# LCD_backpack.net
KiCad netlist of a schematic drawn in EAGLE
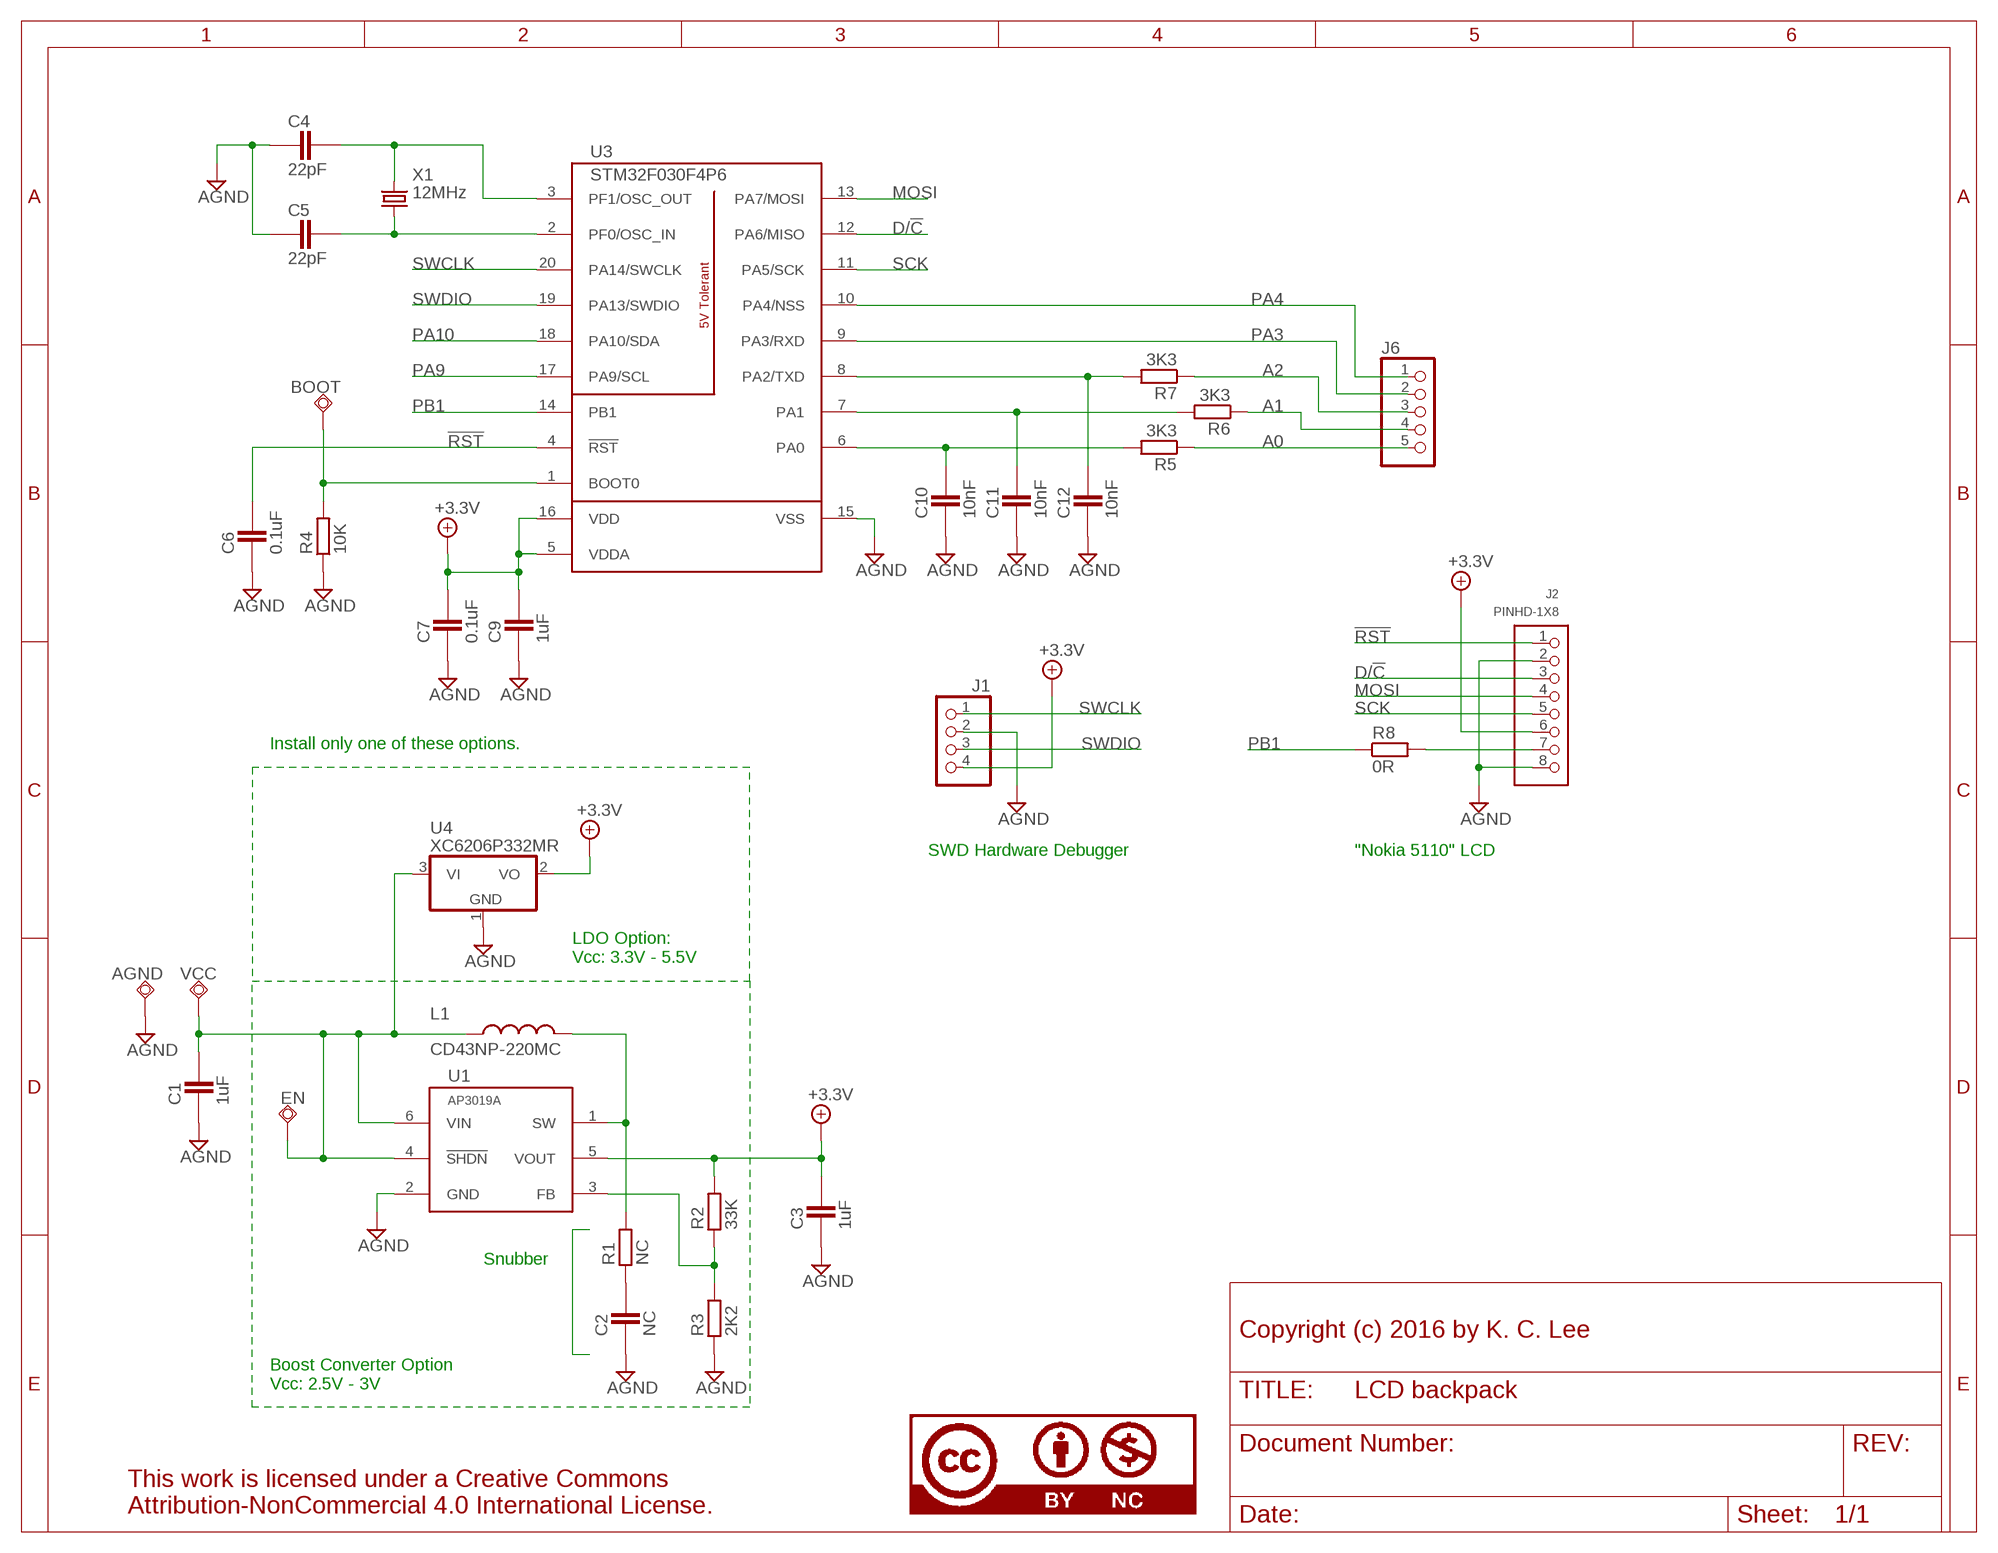
[diagram p0: schematic, sheet 1]

(export (version "E")
  (design (tool "Eeschema 10.0.6"))
  (components
    (comp (ref "AGND")
      (value "TPSQTP10SQ")
      (footprint "eagle-import:TP10SQ")
      (fields (field (name "PARTNO") "TESTPAD"))
      (libsource (lib "eagle-import") (part "TPSQTP10SQ"))
    )
    (comp (ref "BOOT")
      (value "TPSQTP10SQ")
      (footprint "eagle-import:TP10SQ")
      (fields (field (name "PARTNO") "TESTPAD"))
      (libsource (lib "eagle-import") (part "TPSQTP10SQ"))
    )
    (comp (ref "C1")
      (value "1uF")
      (footprint "eagle-import:CAPC1608X92N")
      (fields (field (name "PARTNO") "STOCK: 1UF/10V 20% TDK"))
      (libsource (lib "eagle-import") (part "CAPACITOR_0603"))
    )
    (comp (ref "C2")
      (value "NC")
      (footprint "eagle-import:CAPC1608X92N")
      (libsource (lib "eagle-import") (part "CAPACITOR_0603"))
    )
    (comp (ref "C3")
      (value "1uF")
      (footprint "eagle-import:CAPC1608X92N")
      (fields (field (name "PARTNO") "STOCK: 1UF/10V 20% TDK"))
      (libsource (lib "eagle-import") (part "CAPACITOR_0603"))
    )
    (comp (ref "C4")
      (value "22pF")
      (footprint "eagle-import:CAPC1608X92N")
      (libsource (lib "eagle-import") (part "CAPACITOR_0603"))
    )
    (comp (ref "C5")
      (value "22pF")
      (footprint "eagle-import:CAPC1608X92N")
      (libsource (lib "eagle-import") (part "CAPACITOR_0603"))
    )
    (comp (ref "C6")
      (value "0.1uF")
      (footprint "eagle-import:CAPC1608X92N")
      (libsource (lib "eagle-import") (part "CAPACITOR_0603"))
    )
    (comp (ref "C7")
      (value "0.1uF")
      (footprint "eagle-import:CAPC1608X92N")
      (libsource (lib "eagle-import") (part "CAPACITOR_0603"))
    )
    (comp (ref "C9")
      (value "1uF")
      (footprint "eagle-import:CAPC1608X92N")
      (fields (field (name "PARTNO") "STOCK: 1UF/10V 20% TDK"))
      (libsource (lib "eagle-import") (part "CAPACITOR_0603"))
    )
    (comp (ref "C10")
      (value "10nF")
      (footprint "eagle-import:CAPC1608X92N")
      (libsource (lib "eagle-import") (part "CAPACITOR_0603"))
    )
    (comp (ref "C11")
      (value "10nF")
      (footprint "eagle-import:CAPC1608X92N")
      (libsource (lib "eagle-import") (part "CAPACITOR_0603"))
    )
    (comp (ref "C12")
      (value "10nF")
      (footprint "eagle-import:CAPC1608X92N")
      (libsource (lib "eagle-import") (part "CAPACITOR_0603"))
    )
    (comp (ref "EN")
      (value "TPSQTP06SQ")
      (footprint "eagle-import:TP06SQ")
      (fields (field (name "PARTNO") "TESTPAD"))
      (libsource (lib "eagle-import") (part "TPSQTP06SQ"))
    )
    (comp (ref "J1")
      (value "PINHD-1X4_2.54")
      (footprint "eagle-import:1X04")
      (fields (field (name "PARTNO") "1x04 header 2.54mm"))
      (libsource (lib "eagle-import") (part "PINHD-1X4_2.54"))
    )
    (comp (ref "J2")
      (value "PINHD-1X8")
      (footprint "eagle-import:1X08")
      (fields (field (name "PARTNO") "1x08 header 2.54mm"))
      (libsource (lib "eagle-import") (part "PINHD-1X8"))
    )
    (comp (ref "J6")
      (value "PINHD-1X5_2.00")
      (footprint "eagle-import:1X05M")
      (fields (field (name "PARTNO") "1X5 header 2MM"))
      (libsource (lib "eagle-import") (part "PINHD-1X5_2.00"))
    )
    (comp (ref "L1")
      (value "CD43NP-220MC")
      (footprint "eagle-import:CD43")
      (fields (field (name "PARTNO") "DK: 587-1626-1-ND"))
      (libsource (lib "eagle-import") (part "CD43"))
    )
    (comp (ref "LICENSE1")
      (value "CC-BY-NCNONE")
      (footprint "eagle-import:CC-NONE")
      (libsource (lib "eagle-import") (part "CC-BY-NCNONE"))
    )
    (comp (ref "R1")
      (value "NC")
      (footprint "eagle-import:RESC1608X55N")
      (libsource (lib "eagle-import") (part "RESISTOR_0603"))
    )
    (comp (ref "R2")
      (value "33K")
      (footprint "eagle-import:RESC1608X55N")
      (libsource (lib "eagle-import") (part "RESISTOR_0603"))
    )
    (comp (ref "R3")
      (value "2K2")
      (footprint "eagle-import:RESC1608X55N")
      (libsource (lib "eagle-import") (part "RESISTOR_0603"))
    )
    (comp (ref "R4")
      (value "10K")
      (footprint "eagle-import:RESC1608X55N")
      (libsource (lib "eagle-import") (part "RESISTOR_0603"))
    )
    (comp (ref "R5")
      (value "3K3")
      (footprint "eagle-import:RESC1608X55N")
      (libsource (lib "eagle-import") (part "RESISTOR_0603"))
    )
    (comp (ref "R6")
      (value "3K3")
      (footprint "eagle-import:RESC1608X55N")
      (libsource (lib "eagle-import") (part "RESISTOR_0603"))
    )
    (comp (ref "R7")
      (value "3K3")
      (footprint "eagle-import:RESC1608X55N")
      (libsource (lib "eagle-import") (part "RESISTOR_0603"))
    )
    (comp (ref "R8")
      (value "0R")
      (footprint "eagle-import:RESC1608X55N")
      (libsource (lib "eagle-import") (part "RESISTOR_0603"))
    )
    (comp (ref "U1")
      (value "AP3019A")
      (footprint "eagle-import:SOT26")
      (fields (field (name "PARTNO") "AP3019AKTR-G1"))
      (libsource (lib "eagle-import") (part "AP3019"))
    )
    (comp (ref "U3")
      (value "STM32F030F4P6")
      (footprint "eagle-import:TSSOP20")
      (libsource (lib "eagle-import") (part "STM32F030F4P6"))
    )
    (comp (ref "U4")
      (value "XC6206P332MR")
      (footprint "eagle-import:SOT95P280X135-3N")
      (libsource (lib "eagle-import") (part "MCP1700/TT"))
    )
    (comp (ref "VCC")
      (value "TPSQTP10SQ")
      (footprint "eagle-import:TP10SQ")
      (fields (field (name "PARTNO") "TESTPAD"))
      (libsource (lib "eagle-import") (part "TPSQTP10SQ"))
    )
    (comp (ref "X1")
      (value "12MHz")
      (footprint "eagle-import:HC49U-V")
      (libsource (lib "eagle-import") (part "CRYSTALHC49U-V"))
    )
  )
  (nets
    (net (code "1") (name "+3.3V") (class "Default")
      (node (ref "C3") (pin "2") (pinfunction "2_2") (pintype "passive"))
      (node (ref "C7") (pin "2") (pinfunction "2_2") (pintype "passive"))
      (node (ref "C9") (pin "2") (pinfunction "2_2") (pintype "passive"))
      (node (ref "J1") (pin "4") (pinfunction "4_4") (pintype "passive"))
      (node (ref "J2") (pin "6") (pinfunction "P$6_6") (pintype "bidirectional"))
      (node (ref "R2") (pin "2") (pinfunction "2_2") (pintype "passive"))
      (node (ref "U1") (pin "5") (pinfunction "VOUT_5") (pintype "bidirectional"))
      (node (ref "U3") (pin "16") (pinfunction "VDD_16") (pintype "input"))
      (node (ref "U3") (pin "5") (pinfunction "VDDA_5") (pintype "input"))
      (node (ref "U4") (pin "2") (pinfunction "VO_2") (pintype "passive"))
    )
    (net (code "2") (name "/A0") (class "Default")
      (node (ref "J6") (pin "5") (pinfunction "5_5") (pintype "passive"))
      (node (ref "R5") (pin "1") (pinfunction "1_1") (pintype "passive"))
    )
    (net (code "3") (name "/A1") (class "Default")
      (node (ref "J6") (pin "4") (pinfunction "4_4") (pintype "passive"))
      (node (ref "R6") (pin "1") (pinfunction "1_1") (pintype "passive"))
    )
    (net (code "4") (name "/A2") (class "Default")
      (node (ref "J6") (pin "3") (pinfunction "3_3") (pintype "passive"))
      (node (ref "R7") (pin "1") (pinfunction "1_1") (pintype "passive"))
    )
    (net (code "5") (name "/D{slash}~{C}") (class "Default")
      (node (ref "J2") (pin "3") (pinfunction "P$3_3") (pintype "bidirectional"))
      (node (ref "U3") (pin "12") (pinfunction "PA6/MISO_12") (pintype "bidirectional"))
    )
    (net (code "6") (name "/MOSI") (class "Default")
      (node (ref "J2") (pin "4") (pinfunction "P$4_4") (pintype "bidirectional"))
      (node (ref "U3") (pin "13") (pinfunction "PA7/MOSI_13") (pintype "bidirectional"))
    )
    (net (code "8") (name "/PA3") (class "Default")
      (node (ref "J6") (pin "2") (pinfunction "2_2") (pintype "passive"))
      (node (ref "U3") (pin "9") (pinfunction "PA3/RXD_9") (pintype "bidirectional"))
    )
    (net (code "9") (name "/PA4") (class "Default")
      (node (ref "J6") (pin "1") (pinfunction "1_1") (pintype "passive"))
      (node (ref "U3") (pin "10") (pinfunction "PA4/NSS_10") (pintype "bidirectional"))
    )
    (net (code "10") (name "/PA9") (class "Default")
      (node (ref "U3") (pin "17") (pinfunction "PA9/SCL_17") (pintype "bidirectional"))
    )
    (net (code "11") (name "/PA10") (class "Default")
      (node (ref "U3") (pin "18") (pinfunction "PA10/SDA_18") (pintype "bidirectional"))
    )
    (net (code "12") (name "/PB1") (class "Default")
      (node (ref "R8") (pin "1") (pinfunction "1_1") (pintype "passive"))
      (node (ref "U3") (pin "14") (pinfunction "PB1_14") (pintype "bidirectional"))
    )
    (net (code "13") (name "/SCK") (class "Default")
      (node (ref "J2") (pin "5") (pinfunction "P$5_5") (pintype "bidirectional"))
      (node (ref "U3") (pin "11") (pinfunction "PA5/SCK_11") (pintype "bidirectional"))
    )
    (net (code "14") (name "/SWCLK") (class "Default")
      (node (ref "J1") (pin "1") (pinfunction "1_1") (pintype "passive"))
      (node (ref "U3") (pin "20") (pinfunction "PA14/SWCLK_20") (pintype "bidirectional"))
    )
    (net (code "15") (name "/SWDIO") (class "Default")
      (node (ref "J1") (pin "3") (pinfunction "3_3") (pintype "passive"))
      (node (ref "U3") (pin "19") (pinfunction "PA13/SWDIO_19") (pintype "bidirectional"))
    )
    (net (code "16") (name "/~{RST}") (class "Default")
      (node (ref "C6") (pin "2") (pinfunction "2_2") (pintype "passive"))
      (node (ref "J2") (pin "1") (pinfunction "P$1_1") (pintype "bidirectional"))
      (node (ref "U3") (pin "4") (pinfunction "~{RST}_4") (pintype "input"))
    )
    (net (code "17") (name "AGND") (class "Default")
      (node (ref "AGND") (pin "TP") (pinfunction "TP_TP") (pintype "input"))
      (node (ref "C1") (pin "1") (pinfunction "1_1") (pintype "passive"))
      (node (ref "C10") (pin "1") (pinfunction "1_1") (pintype "passive"))
      (node (ref "C11") (pin "1") (pinfunction "1_1") (pintype "passive"))
      (node (ref "C12") (pin "1") (pinfunction "1_1") (pintype "passive"))
      (node (ref "C2") (pin "1") (pinfunction "1_1") (pintype "passive"))
      (node (ref "C3") (pin "1") (pinfunction "1_1") (pintype "passive"))
      (node (ref "C4") (pin "1") (pinfunction "1_1") (pintype "passive"))
      (node (ref "C5") (pin "1") (pinfunction "1_1") (pintype "passive"))
      (node (ref "C6") (pin "1") (pinfunction "1_1") (pintype "passive"))
      (node (ref "C7") (pin "1") (pinfunction "1_1") (pintype "passive"))
      (node (ref "C9") (pin "1") (pinfunction "1_1") (pintype "passive"))
      (node (ref "J1") (pin "2") (pinfunction "2_2") (pintype "passive"))
      (node (ref "J2") (pin "2") (pinfunction "P$2_2") (pintype "bidirectional"))
      (node (ref "J2") (pin "8") (pinfunction "P$8_8") (pintype "bidirectional"))
      (node (ref "R3") (pin "1") (pinfunction "1_1") (pintype "passive"))
      (node (ref "R4") (pin "1") (pinfunction "1_1") (pintype "passive"))
      (node (ref "U1") (pin "2") (pinfunction "GND_2") (pintype "bidirectional"))
      (node (ref "U3") (pin "15") (pinfunction "VSS_15") (pintype "input"))
      (node (ref "U4") (pin "1") (pinfunction "GND_1") (pintype "passive"))
    )
    (net (code "18") (name "Net-(C2-Pad2)") (class "Default")
      (node (ref "C2") (pin "2") (pinfunction "2_2") (pintype "passive"))
      (node (ref "R1") (pin "1") (pinfunction "1_1") (pintype "passive"))
    )
    (net (code "19") (name "Net-(J2-P$7)") (class "Default")
      (node (ref "J2") (pin "7") (pinfunction "P$7_7") (pintype "bidirectional"))
      (node (ref "R8") (pin "2") (pinfunction "2_2") (pintype "passive"))
    )
    (net (code "20") (name "Net-(U1-FB)") (class "Default")
      (node (ref "R2") (pin "1") (pinfunction "1_1") (pintype "passive"))
      (node (ref "R3") (pin "2") (pinfunction "2_2") (pintype "passive"))
      (node (ref "U1") (pin "3") (pinfunction "FB_3") (pintype "bidirectional"))
    )
    (net (code "21") (name "Net-(U1-SW)") (class "Default")
      (node (ref "L1") (pin "1") (pinfunction "1_1") (pintype "passive"))
      (node (ref "R1") (pin "2") (pinfunction "2_2") (pintype "passive"))
      (node (ref "U1") (pin "1") (pinfunction "SW_1") (pintype "bidirectional"))
    )
    (net (code "22") (name "Net-(U1-VIN)") (class "Default")
      (node (ref "C1") (pin "2") (pinfunction "2_2") (pintype "passive"))
      (node (ref "EN") (pin "TP") (pinfunction "TP_TP") (pintype "input"))
      (node (ref "L1") (pin "2") (pinfunction "2_2") (pintype "passive"))
      (node (ref "U1") (pin "4") (pinfunction "~{SHDN}_4") (pintype "bidirectional"))
      (node (ref "U1") (pin "6") (pinfunction "VIN_6") (pintype "bidirectional"))
      (node (ref "U4") (pin "3") (pinfunction "VI_3") (pintype "input"))
      (node (ref "VCC") (pin "TP") (pinfunction "TP_TP") (pintype "input"))
    )
    (net (code "23") (name "Net-(U3-BOOT0)") (class "Default")
      (node (ref "BOOT") (pin "TP") (pinfunction "TP_TP") (pintype "input"))
      (node (ref "R4") (pin "2") (pinfunction "2_2") (pintype "passive"))
      (node (ref "U3") (pin "1") (pinfunction "BOOT0_1") (pintype "input"))
    )
    (net (code "24") (name "Net-(U3-PA0)") (class "Default")
      (node (ref "C10") (pin "2") (pinfunction "2_2") (pintype "passive"))
      (node (ref "R5") (pin "2") (pinfunction "2_2") (pintype "passive"))
      (node (ref "U3") (pin "6") (pinfunction "PA0_6") (pintype "bidirectional"))
    )
    (net (code "25") (name "Net-(U3-PA1)") (class "Default")
      (node (ref "C11") (pin "2") (pinfunction "2_2") (pintype "passive"))
      (node (ref "R6") (pin "2") (pinfunction "2_2") (pintype "passive"))
      (node (ref "U3") (pin "7") (pinfunction "PA1_7") (pintype "bidirectional"))
    )
    (net (code "26") (name "Net-(U3-PA2{slash}TXD)") (class "Default")
      (node (ref "C12") (pin "2") (pinfunction "2_2") (pintype "passive"))
      (node (ref "R7") (pin "2") (pinfunction "2_2") (pintype "passive"))
      (node (ref "U3") (pin "8") (pinfunction "PA2/TXD_8") (pintype "bidirectional"))
    )
    (net (code "27") (name "Net-(U3-PF0{slash}OSC_IN)") (class "Default")
      (node (ref "C5") (pin "2") (pinfunction "2_2") (pintype "passive"))
      (node (ref "U3") (pin "2") (pinfunction "PF0/OSC_IN_2") (pintype "input"))
      (node (ref "X1") (pin "1") (pinfunction "1_1") (pintype "passive"))
    )
    (net (code "28") (name "Net-(U3-PF1{slash}OSC_OUT)") (class "Default")
      (node (ref "C4") (pin "2") (pinfunction "2_2") (pintype "passive"))
      (node (ref "U3") (pin "3") (pinfunction "PF1/OSC_OUT_3") (pintype "output"))
      (node (ref "X1") (pin "2") (pinfunction "2_2") (pintype "passive"))
    )
  )
)
